# openSX70_ALPHA_V6_2-20181009.net
KiCad netlist of a schematic drawn in EAGLE
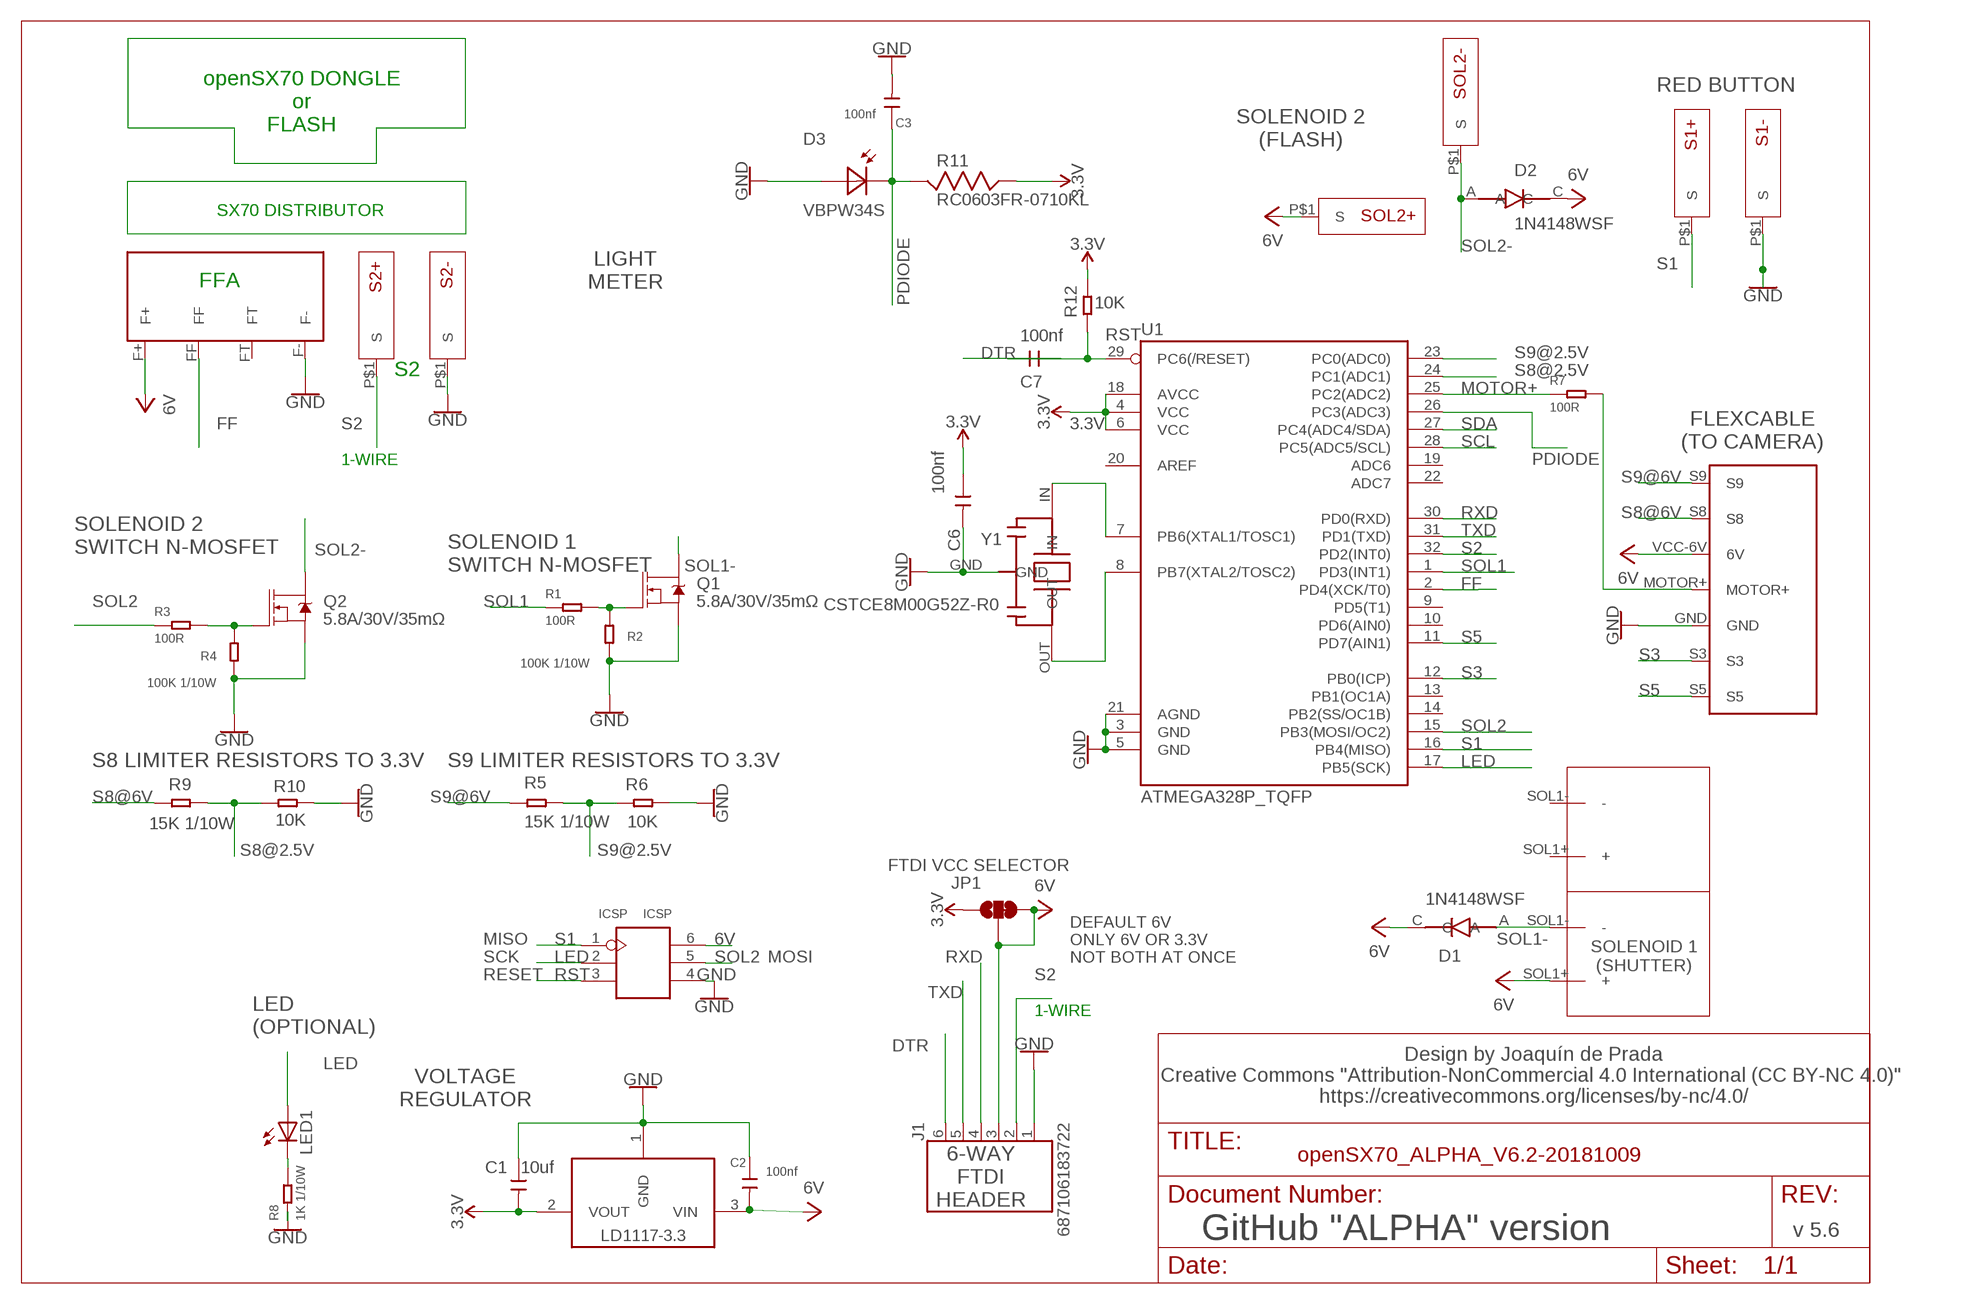
[diagram p0: schematic, sheet 1]

(export (version "E")
  (design (tool "Eeschema 10.0.6"))
  (components
    (comp (ref "C1")
      (value "10uf")
      (footprint "eagle-import:C0603")
      (fields (field (name "MPN") "CC0603KRX5R6BB106"))
      (libsource (lib "eagle-import") (part "CERAMIC-10UF-10V-10%-X5R(0603)"))
    )
    (comp (ref "C2")
      (value "100nf")
      (footprint "eagle-import:C0603")
      (fields (field (name "MPN") "CC0603KRX7R9BB104"))
      (libsource (lib "eagle-import") (part "CERAMIC-100NF-50V-10%-X7R(0603)"))
    )
    (comp (ref "C3")
      (value "100nf")
      (footprint "eagle-import:C0603")
      (fields (field (name "MPN") "CC0603KRX7R9BB104"))
      (libsource (lib "eagle-import") (part "CERAMIC-100NF-50V-10%-X7R(0603)"))
    )
    (comp (ref "C6")
      (value "100nf")
      (footprint "eagle-import:C0603")
      (fields (field (name "MPN") "CC0603KRX7R9BB104"))
      (libsource (lib "eagle-import") (part "CERAMIC-100NF-50V-10%-X7R(0603)"))
    )
    (comp (ref "C7")
      (value "100nf")
      (footprint "eagle-import:C0603")
      (fields (field (name "MPN") "CC0603KRX7R9BB104"))
      (libsource (lib "eagle-import") (part "CERAMIC-100NF-50V-10%-X7R(0603)"))
    )
    (comp (ref "D1")
      (value "1N4148WSF")
      (footprint "eagle-import:SODFL2512X100N")
      (fields (field (name "MANUFACTURER") "Fairchild Semiconductor"))
      (libsource (lib "eagle-import") (part "1N4148WS"))
    )
    (comp (ref "D2")
      (value "1N4148WSF")
      (footprint "eagle-import:SODFL2512X100N")
      (fields (field (name "MANUFACTURER") "Fairchild Semiconductor"))
      (libsource (lib "eagle-import") (part "1N4148WS"))
    )
    (comp (ref "D3")
      (value "VBPW34S")
      (footprint "eagle-import:SOD6439X130N")
      (fields (field (name "DIGI-KEY_PART_NUMBER") "751-1500-1-ND") (field (name "MF") "Vishay"))
      (libsource (lib "eagle-import") (part "VBPW34S"))
    )
    (comp (ref "ICSP")
      (value "ICSP")
      (footprint "eagle-import:H2X3-2.54")
      (libsource (lib "eagle-import") (part "ICSP"))
    )
    (comp (ref "J1")
      (value "687106183722")
      (footprint "eagle-import:687106183722")
      (fields (field (name "MF") "Wurth Electronics"))
      (libsource (lib "eagle-import") (part "687106183722"))
    )
    (comp (ref "JP1")
      (value "FTDI VCC SELECTOR")
      (footprint "eagle-import:SMT-JUMPER_3_1-NC_TRACE_SILK")
      (libsource (lib "eagle-import") (part "JUMPER-SMT_3_1-NC_TRACE_SILK"))
    )
    (comp (ref "LD11172.5V")
      (value "LD1117 2.5V")
      (footprint "eagle-import:SOT223")
      (fields (field (name "MF") "Advanced Monolithic Systems") (field (name "MP") "AMS1117-5.0"))
      (libsource (lib "eagle-import") (part "LD1117-3.3"))
    )
    (comp (ref "LED1")
      (value "LEDCHIPLED_0805")
      (footprint "eagle-import:CHIPLED_0805")
      (libsource (lib "eagle-import") (part "LEDCHIPLED_0805"))
    )
    (comp (ref "Q1")
      (value "5.8A/30V/35mΩ")
      (footprint "eagle-import:SOT23-3")
      (libsource (lib "eagle-import") (part "MOSFET-NCH-AO3404A"))
    )
    (comp (ref "Q2")
      (value "5.8A/30V/35mΩ")
      (footprint "eagle-import:SOT23-3")
      (libsource (lib "eagle-import") (part "MOSFET-NCH-AO3404A"))
    )
    (comp (ref "R1")
      (value "100R")
      (footprint "eagle-import:R0603")
      (fields (field (name "MPN") "RC0603JR-07100RL"))
      (libsource (lib "eagle-import") (part "SMD-RES-100R-5%-1/10W(0603)"))
    )
    (comp (ref "R2")
      (value "100K 1/10W")
      (footprint "eagle-import:R0603")
      (fields (field (name "MPN") "RC0603JR-07100KL"))
      (libsource (lib "eagle-import") (part "SMD-RES-100K-5%-1/10W(0603)"))
    )
    (comp (ref "R3")
      (value "100R")
      (footprint "eagle-import:R0603")
      (fields (field (name "MPN") "RC0603JR-07100RL"))
      (libsource (lib "eagle-import") (part "SMD-RES-100R-5%-1/10W(0603)"))
    )
    (comp (ref "R4")
      (value "100K 1/10W")
      (footprint "eagle-import:R0603")
      (fields (field (name "MPN") "RC0603JR-07100KL"))
      (libsource (lib "eagle-import") (part "SMD-RES-100K-5%-1/10W(0603)"))
    )
    (comp (ref "R5")
      (value "15K 1/10W")
      (footprint "eagle-import:R0603")
      (fields (field (name "MPN") "RC0603FR-0715KL"))
      (libsource (lib "eagle-import") (part "SMD-RES-15K-1%-1/10W(0603)"))
    )
    (comp (ref "R6")
      (value "10K")
      (footprint "eagle-import:R0603")
      (fields (field (name "MPN") "RC0603FR-0710KL"))
      (libsource (lib "eagle-import") (part "SMD-RES-10K-1%-1/10W(0603)"))
    )
    (comp (ref "R7")
      (value "100R")
      (footprint "eagle-import:R0603")
      (fields (field (name "MPN") "RC0603JR-07100RL"))
      (libsource (lib "eagle-import") (part "SMD-RES-100R-5%-1/10W(0603)"))
    )
    (comp (ref "R8")
      (value "1K 1/10W")
      (footprint "eagle-import:R0603")
      (fields (field (name "MPN") "RC0603JR-071KL"))
      (libsource (lib "eagle-import") (part "SMD-RES-1K-5%-1/10W(0603)"))
    )
    (comp (ref "R9")
      (value "15K 1/10W")
      (footprint "eagle-import:R0603")
      (fields (field (name "MPN") "RC0603FR-0715KL"))
      (libsource (lib "eagle-import") (part "SMD-RES-15K-1%-1/10W(0603)"))
    )
    (comp (ref "R10")
      (value "10K")
      (footprint "eagle-import:R0603")
      (fields (field (name "MPN") "RC0603FR-0710KL"))
      (libsource (lib "eagle-import") (part "SMD-RES-10K-1%-1/10W(0603)"))
    )
    (comp (ref "R11")
      (value "RC0603FR-0710KL")
      (footprint "eagle-import:RC0603FR-0710KL_RESC1608X55")
      (fields (field (name "MANUFACTURER") "YAGEO"))
      (libsource (lib "eagle-import") (part "RC0603FR-0710KL"))
    )
    (comp (ref "R12")
      (value "10K")
      (footprint "eagle-import:R0603")
      (fields (field (name "MPN") "RC0603FR-0710KL"))
      (libsource (lib "eagle-import") (part "SMD-RES-10K-1%-1/10W(0603)"))
    )
    (comp (ref "S1+")
      (value "SX70-S-PAD-NEW")
      (footprint "eagle-import:SX70-S-PAD2")
      (libsource (lib "eagle-import") (part "SX70-S-PAD-NEW"))
    )
    (comp (ref "S1-")
      (value "SX70-S-PAD-NEW")
      (footprint "eagle-import:SX70-S-PAD2")
      (libsource (lib "eagle-import") (part "SX70-S-PAD-NEW"))
    )
    (comp (ref "S2+")
      (value "SX70-S-PAD-NEW")
      (footprint "eagle-import:SX70-S-PAD2")
      (libsource (lib "eagle-import") (part "SX70-S-PAD-NEW"))
    )
    (comp (ref "S2-")
      (value "SX70-S-PAD-NEW")
      (footprint "eagle-import:SX70-S-PAD2")
      (libsource (lib "eagle-import") (part "SX70-S-PAD-NEW"))
    )
    (comp (ref "SOL1")
      (value "SX70-SOLENOID1-2PADS")
      (footprint "eagle-import:SX70-SOLENOID1-2")
      (libsource (lib "eagle-import") (part "SX70-SOLENOID1-2PADS"))
    )
    (comp (ref "SOL2")
      (value "SX70-SOLENOID1-2PADS")
      (footprint "eagle-import:SX70-SOLENOID1-2")
      (libsource (lib "eagle-import") (part "SX70-SOLENOID1-2PADS"))
    )
    (comp (ref "SOL2+")
      (value "SX70-S-PAD-NEW")
      (footprint "eagle-import:SX70-S-PAD2")
      (libsource (lib "eagle-import") (part "SX70-S-PAD-NEW"))
    )
    (comp (ref "SOL2-")
      (value "SX70-S-PAD-NEW")
      (footprint "eagle-import:SX70-S-PAD2")
      (libsource (lib "eagle-import") (part "SX70-S-PAD-NEW"))
    )
    (comp (ref "U$1")
      (value "SX70-7-PAD")
      (footprint "eagle-import:SX70-7-PAD")
      (libsource (lib "eagle-import") (part "SX70-7-PAD"))
    )
    (comp (ref "U$2")
      (value "FFA")
      (footprint "eagle-import:FFA-PAD-PACKAGE")
      (libsource (lib "eagle-import") (part "SX70-FFA-PAD"))
    )
    (comp (ref "U1")
      (value "ATMEGA328P_TQFP")
      (footprint "eagle-import:TQFP32-08")
      (libsource (lib "eagle-import") (part "ATMEGA328P_TQFP"))
    )
    (comp (ref "Y1")
      (value "CSTCE8M00G52Z-R0")
      (footprint "eagle-import:CFP95P160X100-3N")
      (fields (field (name "MF") "Murata") (field (name "MP") "CSTCE16M0V53-R0"))
      (libsource (lib "eagle-import") (part "CSTCE16M0V53-R0"))
    )
  )
  (nets
    (net (code "1") (name "/DTR") (class "Default")
      (node (ref "C7") (pin "1") (pinfunction "1_1") (pintype "passive"))
      (node (ref "J1") (pin "6") (pinfunction "1_6") (pintype "passive"))
    )
    (net (code "2") (name "/FF") (class "Default")
      (node (ref "U$2") (pin "FF") (pinfunction "FF_FF") (pintype "bidirectional"))
      (node (ref "U1") (pin "2") (pinfunction "PD4(XCK/T0)_2") (pintype "bidirectional"))
    )
    (net (code "3") (name "/LED") (class "Default")
      (node (ref "ICSP") (pin "2") (pinfunction "SCK_2") (pintype "bidirectional"))
      (node (ref "LED1") (pin "A") (pinfunction "A_A") (pintype "passive"))
      (node (ref "U1") (pin "17") (pinfunction "PB5(SCK)_17") (pintype "bidirectional"))
    )
    (net (code "4") (name "/MOTOR+") (class "Default")
      (node (ref "R7") (pin "1") (pinfunction "1_1") (pintype "passive"))
      (node (ref "U1") (pin "25") (pinfunction "PC2(ADC2)_25") (pintype "bidirectional"))
    )
    (net (code "5") (name "/PDIODE") (class "Default")
      (node (ref "C3") (pin "1") (pinfunction "1_1") (pintype "passive"))
      (node (ref "D3") (pin "C") (pinfunction "C_C") (pintype "passive"))
      (node (ref "R11") (pin "1") (pinfunction "1_1") (pintype "passive"))
      (node (ref "U1") (pin "26") (pinfunction "PC3(ADC3)_26") (pintype "bidirectional"))
    )
    (net (code "6") (name "/RST") (class "Default")
      (node (ref "C7") (pin "2") (pinfunction "2_2") (pintype "passive"))
      (node (ref "ICSP") (pin "3") (pinfunction "RST_3") (pintype "bidirectional"))
      (node (ref "R12") (pin "1") (pinfunction "1_1") (pintype "passive"))
      (node (ref "U1") (pin "29") (pinfunction "PC6(/RESET)_29") (pintype "bidirectional"))
    )
    (net (code "7") (name "/RXD") (class "Default")
      (node (ref "J1") (pin "4") (pinfunction "3_4") (pintype "passive"))
      (node (ref "U1") (pin "30") (pinfunction "PD0(RXD)_30") (pintype "bidirectional"))
    )
    (net (code "8") (name "/S1") (class "Default")
      (node (ref "ICSP") (pin "1") (pinfunction "MISO_1") (pintype "bidirectional"))
      (node (ref "S1+") (pin "P$1") (pinfunction "S_P$1") (pintype "bidirectional"))
      (node (ref "U1") (pin "16") (pinfunction "PB4(MISO)_16") (pintype "bidirectional"))
    )
    (net (code "9") (name "/S2") (class "Default")
      (node (ref "J1") (pin "2") (pinfunction "5_2") (pintype "passive"))
      (node (ref "S2+") (pin "P$1") (pinfunction "S_P$1") (pintype "bidirectional"))
      (node (ref "U1") (pin "32") (pinfunction "PD2(INT0)_32") (pintype "bidirectional"))
    )
    (net (code "10") (name "/S3") (class "Default")
      (node (ref "U$1") (pin "S3") (pinfunction "S3_S3") (pintype "bidirectional"))
      (node (ref "U1") (pin "12") (pinfunction "PB0(ICP)_12") (pintype "bidirectional"))
    )
    (net (code "11") (name "/S5") (class "Default")
      (node (ref "U$1") (pin "S5") (pinfunction "S5_S5") (pintype "bidirectional"))
      (node (ref "U1") (pin "11") (pinfunction "PD7(AIN1)_11") (pintype "bidirectional"))
    )
    (net (code "12") (name "/S8@2.5V") (class "Default")
      (node (ref "R10") (pin "1") (pinfunction "1_1") (pintype "passive"))
      (node (ref "R9") (pin "2") (pinfunction "2_2") (pintype "passive"))
      (node (ref "U1") (pin "24") (pinfunction "PC1(ADC1)_24") (pintype "bidirectional"))
    )
    (net (code "13") (name "/S8@6V") (class "Default")
      (node (ref "R9") (pin "1") (pinfunction "1_1") (pintype "passive"))
      (node (ref "U$1") (pin "S8") (pinfunction "S8_S8") (pintype "bidirectional"))
    )
    (net (code "14") (name "/S9@2.5V") (class "Default")
      (node (ref "R5") (pin "2") (pinfunction "2_2") (pintype "passive"))
      (node (ref "R6") (pin "1") (pinfunction "1_1") (pintype "passive"))
      (node (ref "U1") (pin "23") (pinfunction "PC0(ADC0)_23") (pintype "bidirectional"))
    )
    (net (code "15") (name "/S9@6V") (class "Default")
      (node (ref "R5") (pin "1") (pinfunction "1_1") (pintype "passive"))
      (node (ref "U$1") (pin "S9") (pinfunction "S9_S9") (pintype "bidirectional"))
    )
    (net (code "16") (name "/SCL") (class "Default")
      (node (ref "U1") (pin "28") (pinfunction "PC5(ADC5/SCL)_28") (pintype "bidirectional"))
    )
    (net (code "17") (name "/SDA") (class "Default")
      (node (ref "U1") (pin "27") (pinfunction "PC4(ADC4/SDA)_27") (pintype "bidirectional"))
    )
    (net (code "18") (name "/SOL1") (class "Default")
      (node (ref "R1") (pin "1") (pinfunction "1_1") (pintype "passive"))
      (node (ref "U1") (pin "1") (pinfunction "PD3(INT1)_1") (pintype "bidirectional"))
    )
    (net (code "19") (name "/SOL1-") (class "Default")
      (node (ref "D1") (pin "A") (pinfunction "A_A") (pintype "passive"))
      (node (ref "Q1") (pin "3") (pinfunction "D_3") (pintype "bidirectional"))
      (node (ref "SOL1") (pin "SOL1-") (pinfunction "-_SOL1-") (pintype "bidirectional"))
    )
    (net (code "20") (name "/SOL2") (class "Default")
      (node (ref "ICSP") (pin "5") (pinfunction "MOSI_5") (pintype "bidirectional"))
      (node (ref "R3") (pin "1") (pinfunction "1_1") (pintype "passive"))
      (node (ref "U1") (pin "15") (pinfunction "PB3(MOSI/OC2)_15") (pintype "bidirectional"))
    )
    (net (code "21") (name "/SOL2-") (class "Default")
      (node (ref "D2") (pin "A") (pinfunction "A_A") (pintype "passive"))
      (node (ref "Q2") (pin "3") (pinfunction "D_3") (pintype "bidirectional"))
      (node (ref "SOL2-") (pin "P$1") (pinfunction "S_P$1") (pintype "bidirectional"))
    )
    (net (code "22") (name "/TXD") (class "Default")
      (node (ref "J1") (pin "5") (pinfunction "2_5") (pintype "passive"))
      (node (ref "U1") (pin "31") (pinfunction "PD1(TXD)_31") (pintype "bidirectional"))
    )
    (net (code "23") (name "3.3V") (class "Default")
      (node (ref "C1") (pin "2") (pinfunction "2_2") (pintype "passive"))
      (node (ref "C6") (pin "1") (pinfunction "1_1") (pintype "passive"))
      (node (ref "JP1") (pin "1") (pinfunction "1_1") (pintype "passive"))
      (node (ref "LD11172.5V") (pin "2") (pinfunction "VOUT_2") (pintype "bidirectional"))
      (node (ref "R11") (pin "2") (pinfunction "2_2") (pintype "passive"))
      (node (ref "R12") (pin "2") (pinfunction "2_2") (pintype "passive"))
      (node (ref "U1") (pin "18") (pinfunction "AVCC_18") (pintype "bidirectional"))
      (node (ref "U1") (pin "4") (pinfunction "VCC_4") (pintype "bidirectional"))
      (node (ref "U1") (pin "6") (pinfunction "VCC_6") (pintype "bidirectional"))
    )
    (net (code "24") (name "6V") (class "Default")
      (node (ref "C2") (pin "2") (pinfunction "2_2") (pintype "passive"))
      (node (ref "D1") (pin "C") (pinfunction "C_C") (pintype "passive"))
      (node (ref "D2") (pin "C") (pinfunction "C_C") (pintype "passive"))
      (node (ref "ICSP") (pin "6") (pinfunction "VCC_6") (pintype "bidirectional"))
      (node (ref "J1") (pin "3") (pinfunction "4_3") (pintype "passive"))
      (node (ref "JP1") (pin "2") (pinfunction "2_2") (pintype "passive"))
      (node (ref "JP1") (pin "3") (pinfunction "3_3") (pintype "passive"))
      (node (ref "LD11172.5V") (pin "3") (pinfunction "VIN_3") (pintype "bidirectional"))
      (node (ref "SOL1") (pin "SOL1+") (pinfunction "+_SOL1+") (pintype "bidirectional"))
      (node (ref "SOL2+") (pin "P$1") (pinfunction "S_P$1") (pintype "bidirectional"))
      (node (ref "U$1") (pin "VCC-6V") (pinfunction "6V_VCC-6V") (pintype "bidirectional"))
      (node (ref "U$2") (pin "F+") (pinfunction "F+_F+") (pintype "bidirectional"))
    )
    (net (code "25") (name "GND") (class "Default")
      (node (ref "C1") (pin "1") (pinfunction "1_1") (pintype "passive"))
      (node (ref "C2") (pin "1") (pinfunction "1_1") (pintype "passive"))
      (node (ref "C3") (pin "2") (pinfunction "2_2") (pintype "passive"))
      (node (ref "C6") (pin "2") (pinfunction "2_2") (pintype "passive"))
      (node (ref "D3") (pin "A") (pinfunction "A_A") (pintype "passive"))
      (node (ref "ICSP") (pin "4") (pinfunction "GND_4") (pintype "bidirectional"))
      (node (ref "J1") (pin "1") (pinfunction "6_1") (pintype "passive"))
      (node (ref "LD11172.5V") (pin "1") (pinfunction "GND_1") (pintype "bidirectional"))
      (node (ref "Q1") (pin "2") (pinfunction "S_2") (pintype "bidirectional"))
      (node (ref "Q2") (pin "2") (pinfunction "S_2") (pintype "bidirectional"))
      (node (ref "R10") (pin "2") (pinfunction "2_2") (pintype "passive"))
      (node (ref "R2") (pin "1") (pinfunction "1_1") (pintype "passive"))
      (node (ref "R4") (pin "1") (pinfunction "1_1") (pintype "passive"))
      (node (ref "R6") (pin "2") (pinfunction "2_2") (pintype "passive"))
      (node (ref "R8") (pin "1") (pinfunction "1_1") (pintype "passive"))
      (node (ref "S1-") (pin "P$1") (pinfunction "S_P$1") (pintype "bidirectional"))
      (node (ref "S2-") (pin "P$1") (pinfunction "S_P$1") (pintype "bidirectional"))
      (node (ref "U$1") (pin "GND") (pinfunction "GND_GND") (pintype "bidirectional"))
      (node (ref "U$2") (pin "F-") (pinfunction "F-_F-") (pintype "bidirectional"))
      (node (ref "U1") (pin "21") (pinfunction "AGND_21") (pintype "bidirectional"))
      (node (ref "U1") (pin "3") (pinfunction "GND_3") (pintype "bidirectional"))
      (node (ref "U1") (pin "5") (pinfunction "GND_5") (pintype "bidirectional"))
      (node (ref "Y1") (pin "GND") (pinfunction "GND_GND") (pintype "passive"))
    )
    (net (code "26") (name "Net-(LED1-PadC)") (class "Default")
      (node (ref "LED1") (pin "C") (pinfunction "C_C") (pintype "passive"))
      (node (ref "R8") (pin "2") (pinfunction "2_2") (pintype "passive"))
    )
    (net (code "27") (name "Net-(Q1-G)") (class "Default")
      (node (ref "Q1") (pin "1") (pinfunction "G_1") (pintype "bidirectional"))
      (node (ref "R1") (pin "2") (pinfunction "2_2") (pintype "passive"))
      (node (ref "R2") (pin "2") (pinfunction "2_2") (pintype "passive"))
    )
    (net (code "28") (name "Net-(Q2-G)") (class "Default")
      (node (ref "Q2") (pin "1") (pinfunction "G_1") (pintype "bidirectional"))
      (node (ref "R3") (pin "2") (pinfunction "2_2") (pintype "passive"))
      (node (ref "R4") (pin "2") (pinfunction "2_2") (pintype "passive"))
    )
    (net (code "29") (name "Net-(R7-Pad2)") (class "Default")
      (node (ref "R7") (pin "2") (pinfunction "2_2") (pintype "passive"))
      (node (ref "U$1") (pin "MOTOR+") (pinfunction "MOTOR+_MOTOR+") (pintype "bidirectional"))
    )
    (net (code "30") (name "Net-(U1-PB6(XTAL1{slash}TOSC1))") (class "Default")
      (node (ref "U1") (pin "7") (pinfunction "PB6(XTAL1/TOSC1)_7") (pintype "bidirectional"))
      (node (ref "Y1") (pin "IN") (pinfunction "IN_IN") (pintype "input"))
    )
    (net (code "31") (name "Net-(U1-PB7(XTAL2{slash}TOSC2))") (class "Default")
      (node (ref "U1") (pin "8") (pinfunction "PB7(XTAL2/TOSC2)_8") (pintype "bidirectional"))
      (node (ref "Y1") (pin "OUT") (pinfunction "OUT_OUT") (pintype "output"))
    )
    (net (code "32") (name "unconnected-(SOL2-+-PadSOL1+)") (class "Default")
      (node (ref "SOL2") (pin "SOL1+") (pinfunction "+_SOL1+") (pintype "bidirectional"))
    )
    (net (code "33") (name "unconnected-(SOL2---PadSOL1-)") (class "Default")
      (node (ref "SOL2") (pin "SOL1-") (pinfunction "-_SOL1-") (pintype "bidirectional"))
    )
    (net (code "34") (name "unconnected-(U$2-PadFT)") (class "Default")
      (node (ref "U$2") (pin "FT") (pinfunction "FT_FT") (pintype "bidirectional"))
    )
    (net (code "35") (name "unconnected-(U1-ADC6-Pad19)") (class "Default")
      (node (ref "U1") (pin "19") (pinfunction "ADC6_19") (pintype "bidirectional"))
    )
    (net (code "36") (name "unconnected-(U1-ADC7-Pad22)") (class "Default")
      (node (ref "U1") (pin "22") (pinfunction "ADC7_22") (pintype "bidirectional"))
    )
    (net (code "37") (name "unconnected-(U1-AREF-Pad20)") (class "Default")
      (node (ref "U1") (pin "20") (pinfunction "AREF_20") (pintype "bidirectional"))
    )
    (net (code "38") (name "unconnected-(U1-PB1(OC1A)-Pad13)") (class "Default")
      (node (ref "U1") (pin "13") (pinfunction "PB1(OC1A)_13") (pintype "bidirectional"))
    )
    (net (code "39") (name "unconnected-(U1-PB2(SS{slash}OC1B)-Pad14)") (class "Default")
      (node (ref "U1") (pin "14") (pinfunction "PB2(SS/OC1B)_14") (pintype "bidirectional"))
    )
    (net (code "40") (name "unconnected-(U1-PD5(T1)-Pad9)") (class "Default")
      (node (ref "U1") (pin "9") (pinfunction "PD5(T1)_9") (pintype "bidirectional"))
    )
    (net (code "41") (name "unconnected-(U1-PD6(AIN0)-Pad10)") (class "Default")
      (node (ref "U1") (pin "10") (pinfunction "PD6(AIN0)_10") (pintype "bidirectional"))
    )
  )
)
